# AWR2243_Decoupling_Caps.net
KiCad netlist of a schematic drawn in Altium Designer
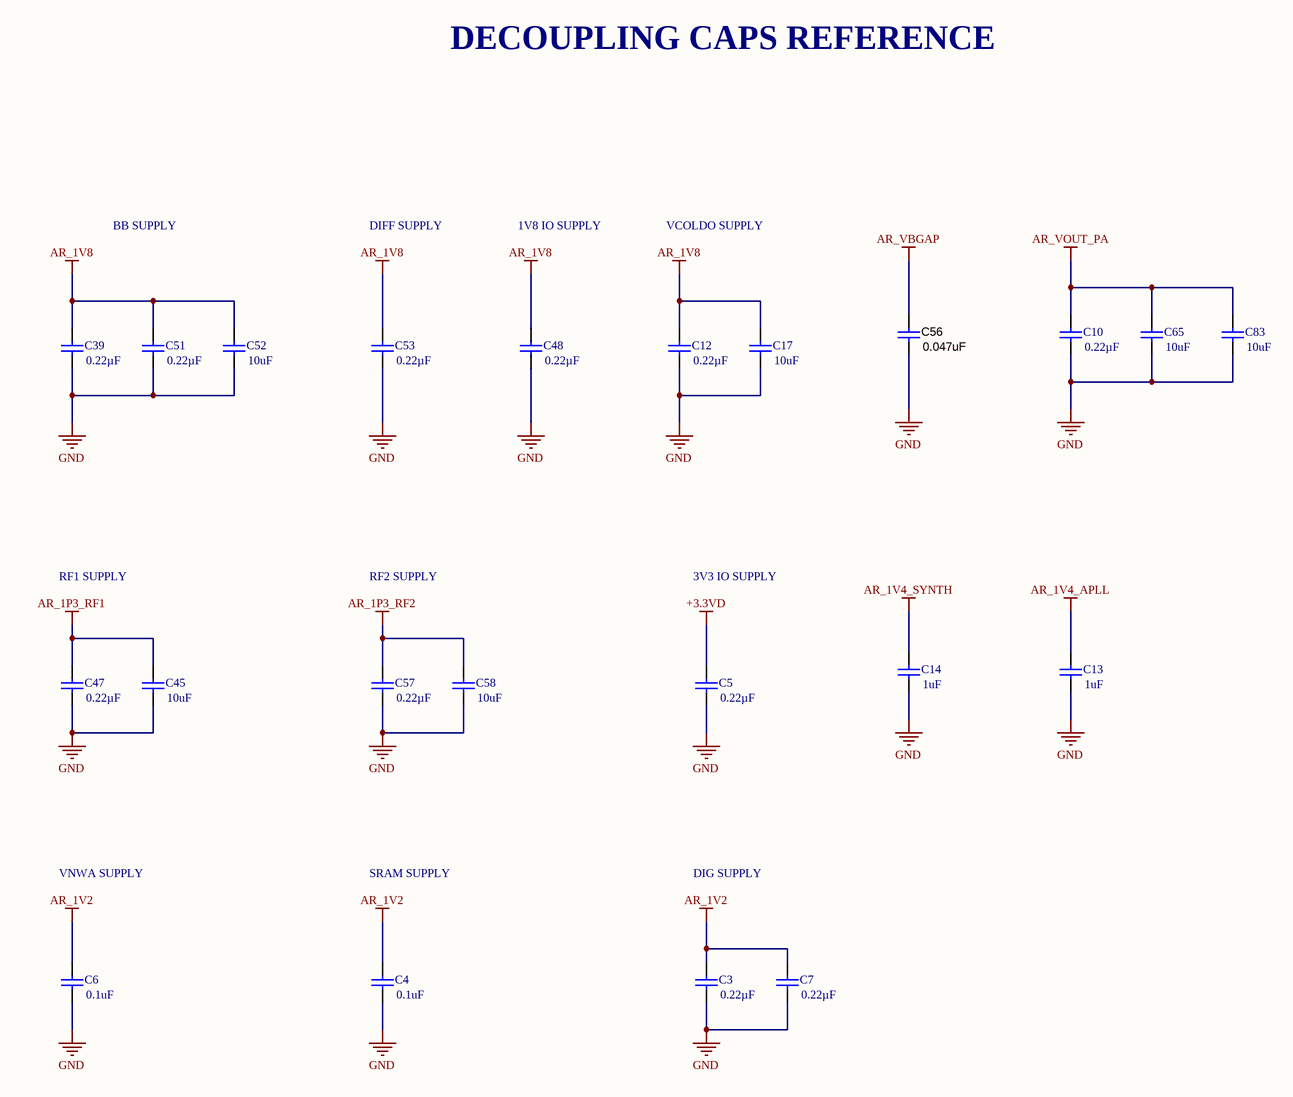
[diagram p0: AWR2243_Decoupling_Caps.SchDoc]

(export (version "E")
  (design (tool "Eeschema 10.0.6"))
  (components
    (comp (ref "C3")
      (value "GCM155R71C224KE02D")
      (footprint "0402L")
      (description "CAP, CERM, 0.22 µF, 16 V,+/- 10%, X7R, AEC-Q200 Grade 1, 0402")
      (fields (field (name "MANUFACTURER") "MuRata") (field (name "VALUEDISPLAYED") "0.22µF"))
      (libsource (lib "Altium Vault - TI") (part "CMP-0078265-1"))
    )
    (comp (ref "C4")
      (value "GCM155R71C104KA55D")
      (footprint "0402L")
      (description "CAP, CERM, 0.1 uF, 16 V, +/- 10%, X7R, 0402")
      (fields
        (field (name "MANUFACTURER") "MuRata")
        (field (name "VALUEDISPLAYED") "0.1uF")
        (field (name "PUBLISHER") "Texas Instruments")
      )
      (libsource (lib "Altium Vault - TI") (part "CMP-0006351-2"))
    )
    (comp (ref "C5")
      (value "GCM155R71C224KE02D")
      (footprint "0402L")
      (description "CAP, CERM, 0.22 µF, 16 V,+/- 10%, X7R, AEC-Q200 Grade 1, 0402")
      (fields (field (name "MANUFACTURER") "MuRata") (field (name "VALUEDISPLAYED") "0.22µF"))
      (libsource (lib "Altium Vault - TI") (part "CMP-0078265-1"))
    )
    (comp (ref "C6")
      (value "GCM155R71C104KA55D")
      (footprint "0402")
      (description "CAP, CERM, 0.1 uF, 16 V, +/- 10%, X7R, 0402")
      (fields
        (field (name "MANUFACTURER") "MuRata")
        (field (name "VALUEDISPLAYED") "0.1uF")
        (field (name "PUBLISHER") "Texas Instruments")
      )
      (libsource (lib "Altium Vault - TI") (part "Capacitor"))
    )
    (comp (ref "C7")
      (value "GCM155R71C224KE02D")
      (footprint "0402L")
      (description "CAP, CERM, 0.22 µF, 16 V,+/- 10%, X7R, AEC-Q200 Grade 1, 0402")
      (fields (field (name "MANUFACTURER") "MuRata") (field (name "VALUEDISPLAYED") "0.22µF"))
      (libsource (lib "Altium Vault - TI") (part "CMP-0078265-1"))
    )
    (comp (ref "C10")
      (value "GCM155R71C224KE02D")
      (footprint "0402")
      (description "CAP, CERM, 0.22 µF, 16 V,+/- 10%, X7R, AEC-Q200 Grade 1, 0402")
      (fields (field (name "MANUFACTURER") "MuRata") (field (name "VALUEDISPLAYED") "0.22µF"))
      (libsource (lib "Altium Vault - TI") (part "Capacitor"))
    )
    (comp (ref "C12")
      (value "GCM155R71C224KE02D")
      (footprint "0402")
      (description "CAP, CERM, 0.22 µF, 16 V,+/- 10%, X7R, AEC-Q200 Grade 1, 0402")
      (fields (field (name "MANUFACTURER") "MuRata") (field (name "VALUEDISPLAYED") "0.22µF"))
      (libsource (lib "Altium Vault - TI") (part "Capacitor"))
    )
    (comp (ref "C13")
      (value "GCM188R71C105KA64D")
      (footprint "0603")
      (description "CAP, CERM, 1 uF, 16 V, +/- 10%, X7R, AEC-Q200 Grade 1, 0603")
      (fields
        (field (name "MANUFACTURER") "MuRata")
        (field (name "VALUEDISPLAYED") "1uF")
        (field (name "PUBLISHER") "Texas Instruments")
      )
      (libsource (lib "Altium Vault - TI") (part "Capacitor"))
    )
    (comp (ref "C14")
      (value "GCM188R71C105KA64D")
      (footprint "0603")
      (description "CAP, CERM, 1 uF, 16 V, +/- 10%, X7R, AEC-Q200 Grade 1, 0603")
      (fields
        (field (name "MANUFACTURER") "MuRata")
        (field (name "VALUEDISPLAYED") "1uF")
        (field (name "PUBLISHER") "Texas Instruments")
      )
      (libsource (lib "Altium Vault - TI") (part "Capacitor"))
    )
    (comp (ref "C17")
      (value "GCM21BR71A106KE22L")
      (footprint "0805_HV")
      (description "CAP, CERM, 10 uF, 10 V, +/- 10%, X7R, 0805")
      (fields
        (field (name "MANUFACTURER") "MuRata")
        (field (name "VALUEDISPLAYED") "10uF")
        (field (name "PUBLISHER") "Texas Instruments")
      )
      (libsource (lib "Altium Vault - TI") (part "Capacitor"))
    )
    (comp (ref "C39")
      (value "GCM155R71C224KE02D")
      (footprint "0402L")
      (description "CAP, CERM, 0.22 µF, 16 V,+/- 10%, X7R, AEC-Q200 Grade 1, 0402")
      (fields (field (name "MANUFACTURER") "MuRata") (field (name "VALUEDISPLAYED") "0.22µF"))
      (libsource (lib "Altium Vault - TI") (part "CMP-0078265-1"))
    )
    (comp (ref "C45")
      (value "GCM21BR71A106KE22L")
      (footprint "0805_HV1")
      (description "CAP, CERM, 10 uF, 10 V, +/- 10%, X7R, 0805")
      (fields
        (field (name "MANUFACTURER") "MuRata")
        (field (name "VALUEDISPLAYED") "10uF")
        (field (name "PUBLISHER") "Texas Instruments")
      )
      (libsource (lib "Altium Vault - TI") (part "CMP-0008017-2"))
    )
    (comp (ref "C47")
      (value "GCM155R71C224KE02D")
      (footprint "0402L")
      (description "CAP, CERM, 0.22 µF, 16 V,+/- 10%, X7R, AEC-Q200 Grade 1, 0402")
      (fields (field (name "MANUFACTURER") "MuRata") (field (name "VALUEDISPLAYED") "0.22µF"))
      (libsource (lib "Altium Vault - TI") (part "CMP-0078265-1"))
    )
    (comp (ref "C48")
      (value "GCM155R71C224KE02D")
      (footprint "0402")
      (description "CAP, CERM, 0.22 µF, 16 V,+/- 10%, X7R, AEC-Q200 Grade 1, 0402")
      (fields (field (name "MANUFACTURER") "MuRata") (field (name "VALUEDISPLAYED") "0.22µF"))
      (libsource (lib "Altium Vault - TI") (part "Capacitor"))
    )
    (comp (ref "C51")
      (value "GCM155R71C224KE02D")
      (footprint "0402")
      (description "CAP, CERM, 0.22 µF, 16 V,+/- 10%, X7R, AEC-Q200 Grade 1, 0402")
      (fields (field (name "MANUFACTURER") "MuRata") (field (name "VALUEDISPLAYED") "0.22µF"))
      (libsource (lib "Altium Vault - TI") (part "Capacitor"))
    )
    (comp (ref "C52")
      (value "GCM21BR71A106KE22L")
      (footprint "0805_HV")
      (description "CAP, CERM, 10 uF, 10 V, +/- 10%, X7R, 0805")
      (fields
        (field (name "MANUFACTURER") "MuRata")
        (field (name "VALUEDISPLAYED") "10uF")
        (field (name "PUBLISHER") "Texas Instruments")
      )
      (libsource (lib "Altium Vault - TI") (part "Capacitor"))
    )
    (comp (ref "C53")
      (value "GCM155R71C224KE02D")
      (footprint "0402")
      (description "CAP, CERM, 0.22 µF, 16 V,+/- 10%, X7R, AEC-Q200 Grade 1, 0402")
      (fields (field (name "MANUFACTURER") "MuRata") (field (name "VALUEDISPLAYED") "0.22µF"))
      (libsource (lib "Altium Vault - TI") (part "Capacitor"))
    )
    (comp (ref "C56")
      (value "CGA2B3X7R1H473K050BB")
      (footprint "0402")
      (description "CAP, CERM, 0.047 uF, 50 V, +/- 10%, X7R, AEC-Q200 Grade 1, 0402")
      (fields
        (field (name "MANUFACTURER") "TDK")
        (field (name "VALUEDISPLAYED") "0.047uF")
        (field (name "PUBLISHER") "Texas Instruments")
      )
      (libsource (lib "Altium Vault - TI") (part "Capacitor"))
    )
    (comp (ref "C57")
      (value "GCM155R71C224KE02D")
      (footprint "0402")
      (description "CAP, CERM, 0.22 µF, 16 V,+/- 10%, X7R, AEC-Q200 Grade 1, 0402")
      (fields (field (name "MANUFACTURER") "MuRata") (field (name "VALUEDISPLAYED") "0.22µF"))
      (libsource (lib "Altium Vault - TI") (part "Capacitor"))
    )
    (comp (ref "C58")
      (value "GCM21BR71A106KE22L")
      (footprint "0805")
      (description "CAP, CERM, 10 uF, 10 V, +/- 10%, X7R, 0805")
      (fields
        (field (name "MANUFACTURER") "MuRata")
        (field (name "VALUEDISPLAYED") "10uF")
        (field (name "PUBLISHER") "Texas Instruments")
      )
      (libsource (lib "Altium Vault - TI") (part "CMP-0008017-2"))
    )
    (comp (ref "C65")
      (value "GCM21BR71A106KE22L")
      (footprint "0805_HV")
      (description "CAP, CERM, 10 uF, 10 V, +/- 10%, X7R, 0805")
      (fields
        (field (name "MANUFACTURER") "MuRata")
        (field (name "VALUEDISPLAYED") "10uF")
        (field (name "PUBLISHER") "Texas Instruments")
      )
      (libsource (lib "Altium Vault - TI") (part "Capacitor"))
    )
    (comp (ref "C83")
      (value "GCM21BR71A106KE22L")
      (footprint "0805_HV")
      (description "CAP, CERM, 10 uF, 10 V, +/- 10%, X7R, 0805")
      (fields
        (field (name "MANUFACTURER") "MuRata")
        (field (name "VALUEDISPLAYED") "10uF")
        (field (name "PUBLISHER") "Texas Instruments")
      )
      (libsource (lib "Altium Vault - TI") (part "Capacitor"))
    )
  )
  (nets
    (net (code "1") (name "+3.3VD") (class "Default")
      (node (ref "C5") (pin "1") (pinfunction "1_1") (pintype "passive"))
    )
    (net (code "2") (name "AR_1P3_RF1") (class "Default")
      (node (ref "C45") (pin "1") (pinfunction "1_1") (pintype "passive"))
      (node (ref "C47") (pin "1") (pinfunction "1_1") (pintype "passive"))
    )
    (net (code "3") (name "AR_1P3_RF2") (class "Default")
      (node (ref "C57") (pin "1") (pinfunction "1_1") (pintype "passive"))
      (node (ref "C58") (pin "1") (pinfunction "1_1") (pintype "passive"))
    )
    (net (code "4") (name "AR_1V2") (class "Default")
      (node (ref "C3") (pin "1") (pinfunction "1_1") (pintype "passive"))
      (node (ref "C4") (pin "1") (pinfunction "1_1") (pintype "passive"))
      (node (ref "C6") (pin "1") (pinfunction "1_1") (pintype "passive"))
      (node (ref "C7") (pin "1") (pinfunction "1_1") (pintype "passive"))
    )
    (net (code "5") (name "AR_1V4_APLL") (class "Default")
      (node (ref "C13") (pin "1") (pinfunction "1_1") (pintype "passive"))
    )
    (net (code "6") (name "AR_1V4_SYNTH") (class "Default")
      (node (ref "C14") (pin "1") (pinfunction "1_1") (pintype "passive"))
    )
    (net (code "7") (name "AR_1V8") (class "Default")
      (node (ref "C12") (pin "1") (pinfunction "1_1") (pintype "passive"))
      (node (ref "C17") (pin "1") (pinfunction "1_1") (pintype "passive"))
      (node (ref "C39") (pin "1") (pinfunction "1_1") (pintype "passive"))
      (node (ref "C48") (pin "1") (pinfunction "1_1") (pintype "passive"))
      (node (ref "C51") (pin "1") (pinfunction "1_1") (pintype "passive"))
      (node (ref "C52") (pin "1") (pinfunction "1_1") (pintype "passive"))
      (node (ref "C53") (pin "1") (pinfunction "1_1") (pintype "passive"))
    )
    (net (code "8") (name "AR_VBGAP") (class "Default")
      (node (ref "C56") (pin "1") (pinfunction "1_1") (pintype "passive"))
    )
    (net (code "9") (name "AR_VOUT_PA") (class "Default")
      (node (ref "C10") (pin "1") (pinfunction "1_1") (pintype "passive"))
      (node (ref "C65") (pin "1") (pinfunction "1_1") (pintype "passive"))
      (node (ref "C83") (pin "1") (pinfunction "1_1") (pintype "passive"))
    )
    (net (code "10") (name "GND") (class "Default")
      (node (ref "C10") (pin "2") (pinfunction "2_2") (pintype "passive"))
      (node (ref "C12") (pin "2") (pinfunction "2_2") (pintype "passive"))
      (node (ref "C13") (pin "2") (pinfunction "2_2") (pintype "passive"))
      (node (ref "C14") (pin "2") (pinfunction "2_2") (pintype "passive"))
      (node (ref "C17") (pin "2") (pinfunction "2_2") (pintype "passive"))
      (node (ref "C3") (pin "2") (pinfunction "2_2") (pintype "passive"))
      (node (ref "C39") (pin "2") (pinfunction "2_2") (pintype "passive"))
      (node (ref "C4") (pin "2") (pinfunction "2_2") (pintype "passive"))
      (node (ref "C45") (pin "2") (pinfunction "2_2") (pintype "passive"))
      (node (ref "C47") (pin "2") (pinfunction "2_2") (pintype "passive"))
      (node (ref "C48") (pin "2") (pinfunction "2_2") (pintype "passive"))
      (node (ref "C5") (pin "2") (pinfunction "2_2") (pintype "passive"))
      (node (ref "C51") (pin "2") (pinfunction "2_2") (pintype "passive"))
      (node (ref "C52") (pin "2") (pinfunction "2_2") (pintype "passive"))
      (node (ref "C53") (pin "2") (pinfunction "2_2") (pintype "passive"))
      (node (ref "C56") (pin "2") (pinfunction "2_2") (pintype "passive"))
      (node (ref "C57") (pin "2") (pinfunction "2_2") (pintype "passive"))
      (node (ref "C58") (pin "2") (pinfunction "2_2") (pintype "passive"))
      (node (ref "C6") (pin "2") (pinfunction "2_2") (pintype "passive"))
      (node (ref "C65") (pin "2") (pinfunction "2_2") (pintype "passive"))
      (node (ref "C7") (pin "2") (pinfunction "2_2") (pintype "passive"))
      (node (ref "C83") (pin "2") (pinfunction "2_2") (pintype "passive"))
    )
  )
)
